# Power_control_shield_v1.net
KiCad netlist of a schematic drawn in EAGLE
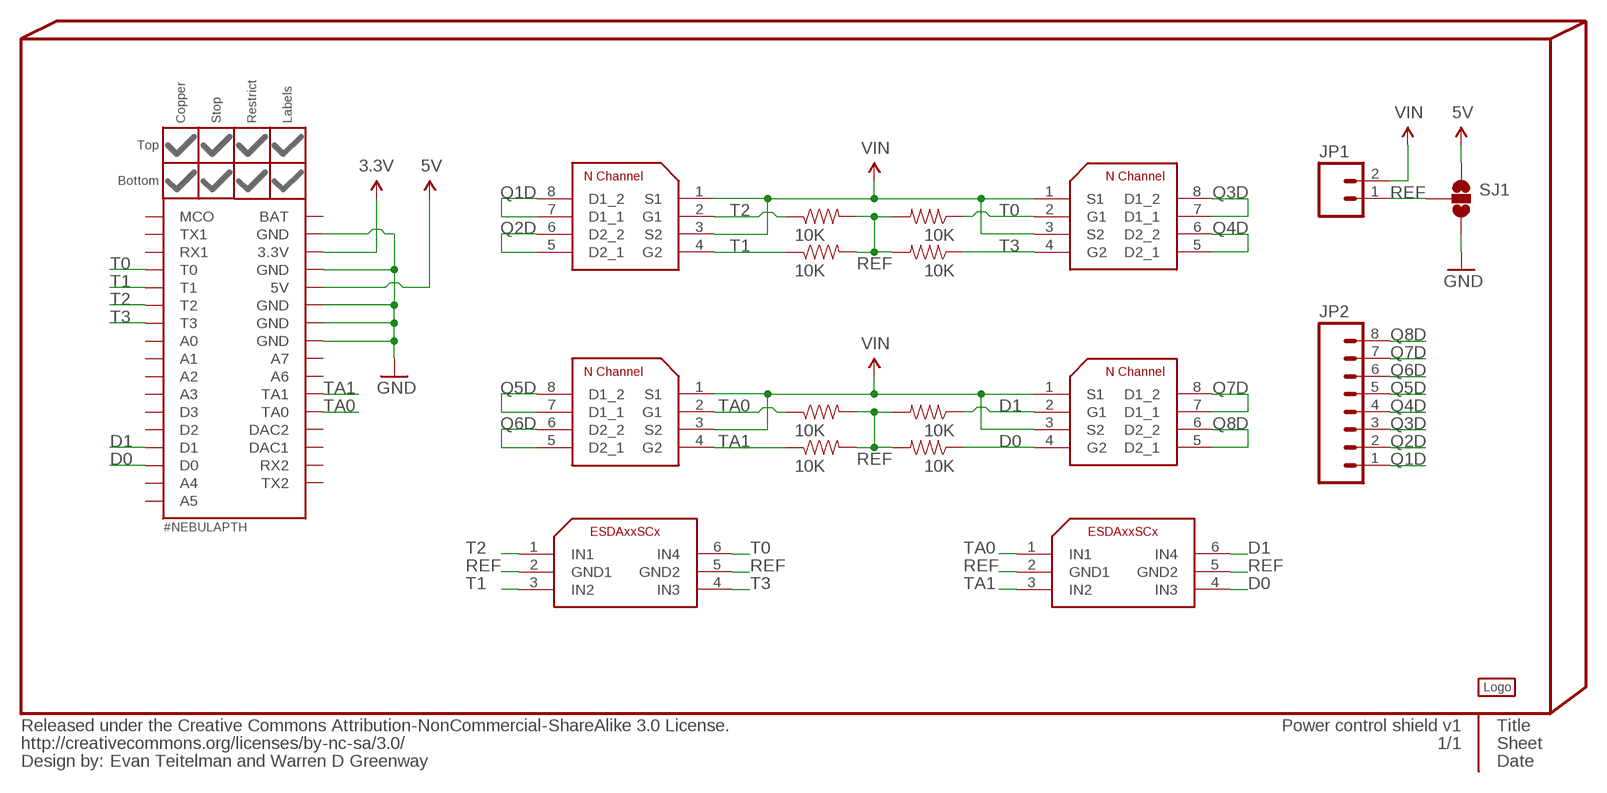
[diagram p0: schematic, sheet 1]

(export (version "E")
  (design (tool "Eeschema 10.0.6"))
  (components
    (comp (ref "INFO2")
      (value "Evan Teitelman and Warren D Greenway")
      (footprint "eagle-import:%CC-NC-SA")
      (libsource (lib "eagle-import") (part "%CC-NC-SA"))
    )
    (comp (ref "JP1")
      (value "M02PTH")
      (footprint "eagle-import:1X02")
      (libsource (lib "eagle-import") (part "M02PTH"))
    )
    (comp (ref "JP2")
      (value "M081X08")
      (footprint "eagle-import:1X08")
      (libsource (lib "eagle-import") (part "M081X08"))
    )
    (comp (ref "LOGO1")
      (value "#LOGOA-THICK")
      (footprint "eagle-import:#LOGOA-THICK")
      (libsource (lib "eagle-import") (part "#LOGOA-THICK"))
    )
    (comp (ref "NEBULA1")
      (value "#NEBULAPTH")
      (footprint "eagle-import:#NEBULA-PTH")
      (libsource (lib "eagle-import") (part "#NEBULAPTH"))
    )
    (comp (ref "NEBULAPART1")
      (value "#NEBULA-PARTLABELS-BOTTOM")
      (footprint "eagle-import:#NEBULA-LABELS-BOTT")
      (libsource (lib "eagle-import") (part "#NEBULA-PARTLABELS-BOTTOM"))
    )
    (comp (ref "R1")
      (value "10K")
      (footprint "eagle-import:0402-RES")
      (libsource (lib "eagle-import") (part "RESISTOR0402-RES"))
    )
    (comp (ref "R2")
      (value "10K")
      (footprint "eagle-import:0402-RES")
      (libsource (lib "eagle-import") (part "RESISTOR0402-RES"))
    )
    (comp (ref "R3")
      (value "10K")
      (footprint "eagle-import:0402-RES")
      (libsource (lib "eagle-import") (part "RESISTOR0402-RES"))
    )
    (comp (ref "R4")
      (value "10K")
      (footprint "eagle-import:0402-RES")
      (libsource (lib "eagle-import") (part "RESISTOR0402-RES"))
    )
    (comp (ref "R9")
      (value "10K")
      (footprint "eagle-import:0402-RES")
      (libsource (lib "eagle-import") (part "RESISTOR0402-RES"))
    )
    (comp (ref "R10")
      (value "10K")
      (footprint "eagle-import:0402-RES")
      (libsource (lib "eagle-import") (part "RESISTOR0402-RES"))
    )
    (comp (ref "R11")
      (value "10K")
      (footprint "eagle-import:0402-RES")
      (libsource (lib "eagle-import") (part "RESISTOR0402-RES"))
    )
    (comp (ref "R12")
      (value "10K")
      (footprint "eagle-import:0402-RES")
      (libsource (lib "eagle-import") (part "RESISTOR0402-RES"))
    )
    (comp (ref "SJ1")
      (value "SOLDERJUMPER_2WAYPASTE2&3")
      (footprint "eagle-import:SJ_3_PASTE2&3")
      (libsource (lib "eagle-import") (part "SOLDERJUMPER_2WAYPASTE2&3"))
    )
    (comp (ref "U$1")
      (value "ESDAXXSC6")
      (footprint "eagle-import:SOT23-6L")
      (libsource (lib "eagle-import") (part "ESDAXXSC6"))
    )
    (comp (ref "U$3")
      (value "ESDAXXSC6")
      (footprint "eagle-import:SOT23-6L")
      (libsource (lib "eagle-import") (part "ESDAXXSC6"))
    )
    (comp (ref "U1")
      (value "TRANSISTOR-VISHAY-SI7288DP")
      (footprint "eagle-import:SOIC8")
      (libsource (lib "eagle-import") (part "TRANSISTOR-VISHAY-SI7288DP"))
    )
    (comp (ref "U2")
      (value "TRANSISTOR-VISHAY-SI7288DP")
      (footprint "eagle-import:SOIC8")
      (libsource (lib "eagle-import") (part "TRANSISTOR-VISHAY-SI7288DP"))
    )
    (comp (ref "U3")
      (value "TRANSISTOR-VISHAY-SI7288DP")
      (footprint "eagle-import:SOIC8")
      (libsource (lib "eagle-import") (part "TRANSISTOR-VISHAY-SI7288DP"))
    )
    (comp (ref "U4")
      (value "TRANSISTOR-VISHAY-SI7288DP")
      (footprint "eagle-import:SOIC8")
      (libsource (lib "eagle-import") (part "TRANSISTOR-VISHAY-SI7288DP"))
    )
  )
  (nets
    (net (code "1") (name "/D0") (class "Default")
      (node (ref "NEBULA1") (pin "D0") (pinfunction "D0_D0") (pintype "bidirectional"))
      (node (ref "R4") (pin "1") (pinfunction "1_1") (pintype "passive"))
      (node (ref "U$3") (pin "4") (pinfunction "IN3_4") (pintype "bidirectional"))
      (node (ref "U4") (pin "4") (pinfunction "G2_4") (pintype "bidirectional"))
    )
    (net (code "2") (name "/D1") (class "Default")
      (node (ref "NEBULA1") (pin "D1") (pinfunction "D1_D1") (pintype "bidirectional"))
      (node (ref "R3") (pin "1") (pinfunction "1_1") (pintype "passive"))
      (node (ref "U$3") (pin "6") (pinfunction "IN4_6") (pintype "bidirectional"))
      (node (ref "U4") (pin "2") (pinfunction "G1_2") (pintype "bidirectional"))
    )
    (net (code "3") (name "/Q1D") (class "Default")
      (node (ref "JP2") (pin "1") (pinfunction "1_1") (pintype "passive"))
      (node (ref "U1") (pin "7") (pinfunction "D1_1_7") (pintype "bidirectional"))
      (node (ref "U1") (pin "8") (pinfunction "D1_2_8") (pintype "bidirectional"))
    )
    (net (code "4") (name "/Q2D") (class "Default")
      (node (ref "JP2") (pin "2") (pinfunction "2_2") (pintype "passive"))
      (node (ref "U1") (pin "5") (pinfunction "D2_1_5") (pintype "bidirectional"))
      (node (ref "U1") (pin "6") (pinfunction "D2_2_6") (pintype "bidirectional"))
    )
    (net (code "5") (name "/Q3D") (class "Default")
      (node (ref "JP2") (pin "3") (pinfunction "3_3") (pintype "passive"))
      (node (ref "U2") (pin "7") (pinfunction "D1_1_7") (pintype "bidirectional"))
      (node (ref "U2") (pin "8") (pinfunction "D1_2_8") (pintype "bidirectional"))
    )
    (net (code "6") (name "/Q4D") (class "Default")
      (node (ref "JP2") (pin "4") (pinfunction "4_4") (pintype "passive"))
      (node (ref "U2") (pin "5") (pinfunction "D2_1_5") (pintype "bidirectional"))
      (node (ref "U2") (pin "6") (pinfunction "D2_2_6") (pintype "bidirectional"))
    )
    (net (code "7") (name "/Q5D") (class "Default")
      (node (ref "JP2") (pin "5") (pinfunction "5_5") (pintype "passive"))
      (node (ref "U3") (pin "7") (pinfunction "D1_1_7") (pintype "bidirectional"))
      (node (ref "U3") (pin "8") (pinfunction "D1_2_8") (pintype "bidirectional"))
    )
    (net (code "8") (name "/Q6D") (class "Default")
      (node (ref "JP2") (pin "6") (pinfunction "6_6") (pintype "passive"))
      (node (ref "U3") (pin "5") (pinfunction "D2_1_5") (pintype "bidirectional"))
      (node (ref "U3") (pin "6") (pinfunction "D2_2_6") (pintype "bidirectional"))
    )
    (net (code "9") (name "/Q7D") (class "Default")
      (node (ref "JP2") (pin "7") (pinfunction "7_7") (pintype "passive"))
      (node (ref "U4") (pin "7") (pinfunction "D1_1_7") (pintype "bidirectional"))
      (node (ref "U4") (pin "8") (pinfunction "D1_2_8") (pintype "bidirectional"))
    )
    (net (code "10") (name "/Q8D") (class "Default")
      (node (ref "JP2") (pin "8") (pinfunction "8_8") (pintype "passive"))
      (node (ref "U4") (pin "5") (pinfunction "D2_1_5") (pintype "bidirectional"))
      (node (ref "U4") (pin "6") (pinfunction "D2_2_6") (pintype "bidirectional"))
    )
    (net (code "11") (name "/REF") (class "Default")
      (node (ref "JP1") (pin "1") (pinfunction "1_1") (pintype "passive"))
      (node (ref "R1") (pin "2") (pinfunction "2_2") (pintype "passive"))
      (node (ref "R10") (pin "2") (pinfunction "2_2") (pintype "passive"))
      (node (ref "R11") (pin "2") (pinfunction "2_2") (pintype "passive"))
      (node (ref "R12") (pin "2") (pinfunction "2_2") (pintype "passive"))
      (node (ref "R2") (pin "2") (pinfunction "2_2") (pintype "passive"))
      (node (ref "R3") (pin "2") (pinfunction "2_2") (pintype "passive"))
      (node (ref "R4") (pin "2") (pinfunction "2_2") (pintype "passive"))
      (node (ref "R9") (pin "2") (pinfunction "2_2") (pintype "passive"))
      (node (ref "SJ1") (pin "2") (pinfunction "2_2") (pintype "passive"))
      (node (ref "U$1") (pin "2") (pinfunction "GND1_2") (pintype "bidirectional"))
      (node (ref "U$1") (pin "5") (pinfunction "GND2_5") (pintype "bidirectional"))
      (node (ref "U$3") (pin "2") (pinfunction "GND1_2") (pintype "bidirectional"))
      (node (ref "U$3") (pin "5") (pinfunction "GND2_5") (pintype "bidirectional"))
    )
    (net (code "12") (name "/T0") (class "Default")
      (node (ref "NEBULA1") (pin "T0") (pinfunction "T0_T0") (pintype "bidirectional"))
      (node (ref "R11") (pin "1") (pinfunction "1_1") (pintype "passive"))
      (node (ref "U$1") (pin "6") (pinfunction "IN4_6") (pintype "bidirectional"))
      (node (ref "U2") (pin "2") (pinfunction "G1_2") (pintype "bidirectional"))
    )
    (net (code "13") (name "/T1") (class "Default")
      (node (ref "NEBULA1") (pin "T1") (pinfunction "T1_T1") (pintype "bidirectional"))
      (node (ref "R10") (pin "1") (pinfunction "1_1") (pintype "passive"))
      (node (ref "U$1") (pin "3") (pinfunction "IN2_3") (pintype "bidirectional"))
      (node (ref "U1") (pin "4") (pinfunction "G2_4") (pintype "bidirectional"))
    )
    (net (code "14") (name "/T2") (class "Default")
      (node (ref "NEBULA1") (pin "T2") (pinfunction "T2_T2") (pintype "bidirectional"))
      (node (ref "R9") (pin "1") (pinfunction "1_1") (pintype "passive"))
      (node (ref "U$1") (pin "1") (pinfunction "IN1_1") (pintype "bidirectional"))
      (node (ref "U1") (pin "2") (pinfunction "G1_2") (pintype "bidirectional"))
    )
    (net (code "15") (name "/T3") (class "Default")
      (node (ref "NEBULA1") (pin "T3") (pinfunction "T3_T3") (pintype "bidirectional"))
      (node (ref "R12") (pin "1") (pinfunction "1_1") (pintype "passive"))
      (node (ref "U$1") (pin "4") (pinfunction "IN3_4") (pintype "bidirectional"))
      (node (ref "U2") (pin "4") (pinfunction "G2_4") (pintype "bidirectional"))
    )
    (net (code "16") (name "/TA0") (class "Default")
      (node (ref "NEBULA1") (pin "TA0") (pinfunction "TA0_TA0") (pintype "bidirectional"))
      (node (ref "R1") (pin "1") (pinfunction "1_1") (pintype "passive"))
      (node (ref "U$3") (pin "1") (pinfunction "IN1_1") (pintype "bidirectional"))
      (node (ref "U3") (pin "2") (pinfunction "G1_2") (pintype "bidirectional"))
    )
    (net (code "17") (name "/TA1") (class "Default")
      (node (ref "NEBULA1") (pin "TA1") (pinfunction "TA1_TA1") (pintype "bidirectional"))
      (node (ref "R2") (pin "1") (pinfunction "1_1") (pintype "passive"))
      (node (ref "U$3") (pin "3") (pinfunction "IN2_3") (pintype "bidirectional"))
      (node (ref "U3") (pin "4") (pinfunction "G2_4") (pintype "bidirectional"))
    )
    (net (code "18") (name "@3.3V") (class "Default")
      (node (ref "NEBULA1") (pin "3.3V") (pinfunction "3.3V_3.3V") (pintype "bidirectional"))
    )
    (net (code "19") (name "@5V") (class "Default")
      (node (ref "NEBULA1") (pin "5V") (pinfunction "5V_5V") (pintype "bidirectional"))
      (node (ref "SJ1") (pin "1") (pinfunction "1_1") (pintype "passive"))
    )
    (net (code "20") (name "@GND") (class "Default")
      (node (ref "NEBULA1") (pin "GND1") (pinfunction "GND_GND1") (pintype "bidirectional"))
      (node (ref "NEBULA1") (pin "GND2") (pinfunction "GND_GND2") (pintype "bidirectional"))
      (node (ref "NEBULA1") (pin "GND3") (pinfunction "GND_GND3") (pintype "bidirectional"))
      (node (ref "NEBULA1") (pin "GND4") (pinfunction "GND_GND4") (pintype "bidirectional"))
      (node (ref "NEBULA1") (pin "GND5") (pinfunction "GND_GND5") (pintype "bidirectional"))
      (node (ref "SJ1") (pin "3") (pinfunction "3_3") (pintype "passive"))
    )
    (net (code "21") (name "@VIN") (class "Default")
      (node (ref "JP1") (pin "2") (pinfunction "2_2") (pintype "passive"))
      (node (ref "U1") (pin "1") (pinfunction "S1_1") (pintype "bidirectional"))
      (node (ref "U1") (pin "3") (pinfunction "S2_3") (pintype "bidirectional"))
      (node (ref "U2") (pin "1") (pinfunction "S1_1") (pintype "bidirectional"))
      (node (ref "U2") (pin "3") (pinfunction "S2_3") (pintype "bidirectional"))
      (node (ref "U3") (pin "1") (pinfunction "S1_1") (pintype "bidirectional"))
      (node (ref "U3") (pin "3") (pinfunction "S2_3") (pintype "bidirectional"))
      (node (ref "U4") (pin "1") (pinfunction "S1_1") (pintype "bidirectional"))
      (node (ref "U4") (pin "3") (pinfunction "S2_3") (pintype "bidirectional"))
    )
    (net (code "22") (name "unconnected-(NEBULA1-PadA0)") (class "Default")
      (node (ref "NEBULA1") (pin "A0") (pinfunction "A0_A0") (pintype "bidirectional"))
    )
    (net (code "23") (name "unconnected-(NEBULA1-PadA1)") (class "Default")
      (node (ref "NEBULA1") (pin "A1") (pinfunction "A1_A1") (pintype "bidirectional"))
    )
    (net (code "24") (name "unconnected-(NEBULA1-PadA2)") (class "Default")
      (node (ref "NEBULA1") (pin "A2") (pinfunction "A2_A2") (pintype "bidirectional"))
    )
    (net (code "25") (name "unconnected-(NEBULA1-PadA3)") (class "Default")
      (node (ref "NEBULA1") (pin "A3") (pinfunction "A3_A3") (pintype "bidirectional"))
    )
    (net (code "26") (name "unconnected-(NEBULA1-PadA4)") (class "Default")
      (node (ref "NEBULA1") (pin "A4") (pinfunction "A4_A4") (pintype "bidirectional"))
    )
    (net (code "27") (name "unconnected-(NEBULA1-PadA5)") (class "Default")
      (node (ref "NEBULA1") (pin "A5") (pinfunction "A5_A5") (pintype "bidirectional"))
    )
    (net (code "28") (name "unconnected-(NEBULA1-PadA6)") (class "Default")
      (node (ref "NEBULA1") (pin "A6") (pinfunction "A6_A6") (pintype "bidirectional"))
    )
    (net (code "29") (name "unconnected-(NEBULA1-PadA7)") (class "Default")
      (node (ref "NEBULA1") (pin "A7") (pinfunction "A7_A7") (pintype "bidirectional"))
    )
    (net (code "30") (name "unconnected-(NEBULA1-PadBAT)") (class "Default")
      (node (ref "NEBULA1") (pin "BAT") (pinfunction "BAT_BAT") (pintype "bidirectional"))
    )
    (net (code "31") (name "unconnected-(NEBULA1-PadD2)") (class "Default")
      (node (ref "NEBULA1") (pin "D2") (pinfunction "D2_D2") (pintype "bidirectional"))
    )
    (net (code "32") (name "unconnected-(NEBULA1-PadD3)") (class "Default")
      (node (ref "NEBULA1") (pin "D3") (pinfunction "D3_D3") (pintype "bidirectional"))
    )
    (net (code "33") (name "unconnected-(NEBULA1-PadDAC1)") (class "Default")
      (node (ref "NEBULA1") (pin "DAC1") (pinfunction "DAC1_DAC1") (pintype "bidirectional"))
    )
    (net (code "34") (name "unconnected-(NEBULA1-PadDAC2)") (class "Default")
      (node (ref "NEBULA1") (pin "DAC2") (pinfunction "DAC2_DAC2") (pintype "bidirectional"))
    )
    (net (code "35") (name "unconnected-(NEBULA1-PadMCO)") (class "Default")
      (node (ref "NEBULA1") (pin "MCO") (pinfunction "MCO_MCO") (pintype "bidirectional"))
    )
    (net (code "36") (name "unconnected-(NEBULA1-RX1-PadCOM1_RX)") (class "Default")
      (node (ref "NEBULA1") (pin "COM1_RX") (pinfunction "RX1_COM1_RX") (pintype "bidirectional"))
    )
    (net (code "37") (name "unconnected-(NEBULA1-RX2-PadCOM2_RX)") (class "Default")
      (node (ref "NEBULA1") (pin "COM2_RX") (pinfunction "RX2_COM2_RX") (pintype "bidirectional"))
    )
    (net (code "38") (name "unconnected-(NEBULA1-TX1-PadCOM1_TX)") (class "Default")
      (node (ref "NEBULA1") (pin "COM1_TX") (pinfunction "TX1_COM1_TX") (pintype "bidirectional"))
    )
    (net (code "39") (name "unconnected-(NEBULA1-TX2-PadCOM2_TX)") (class "Default")
      (node (ref "NEBULA1") (pin "COM2_TX") (pinfunction "TX2_COM2_TX") (pintype "bidirectional"))
    )
  )
)
